# M420C.net
KiCad netlist of a schematic drawn in EAGLE
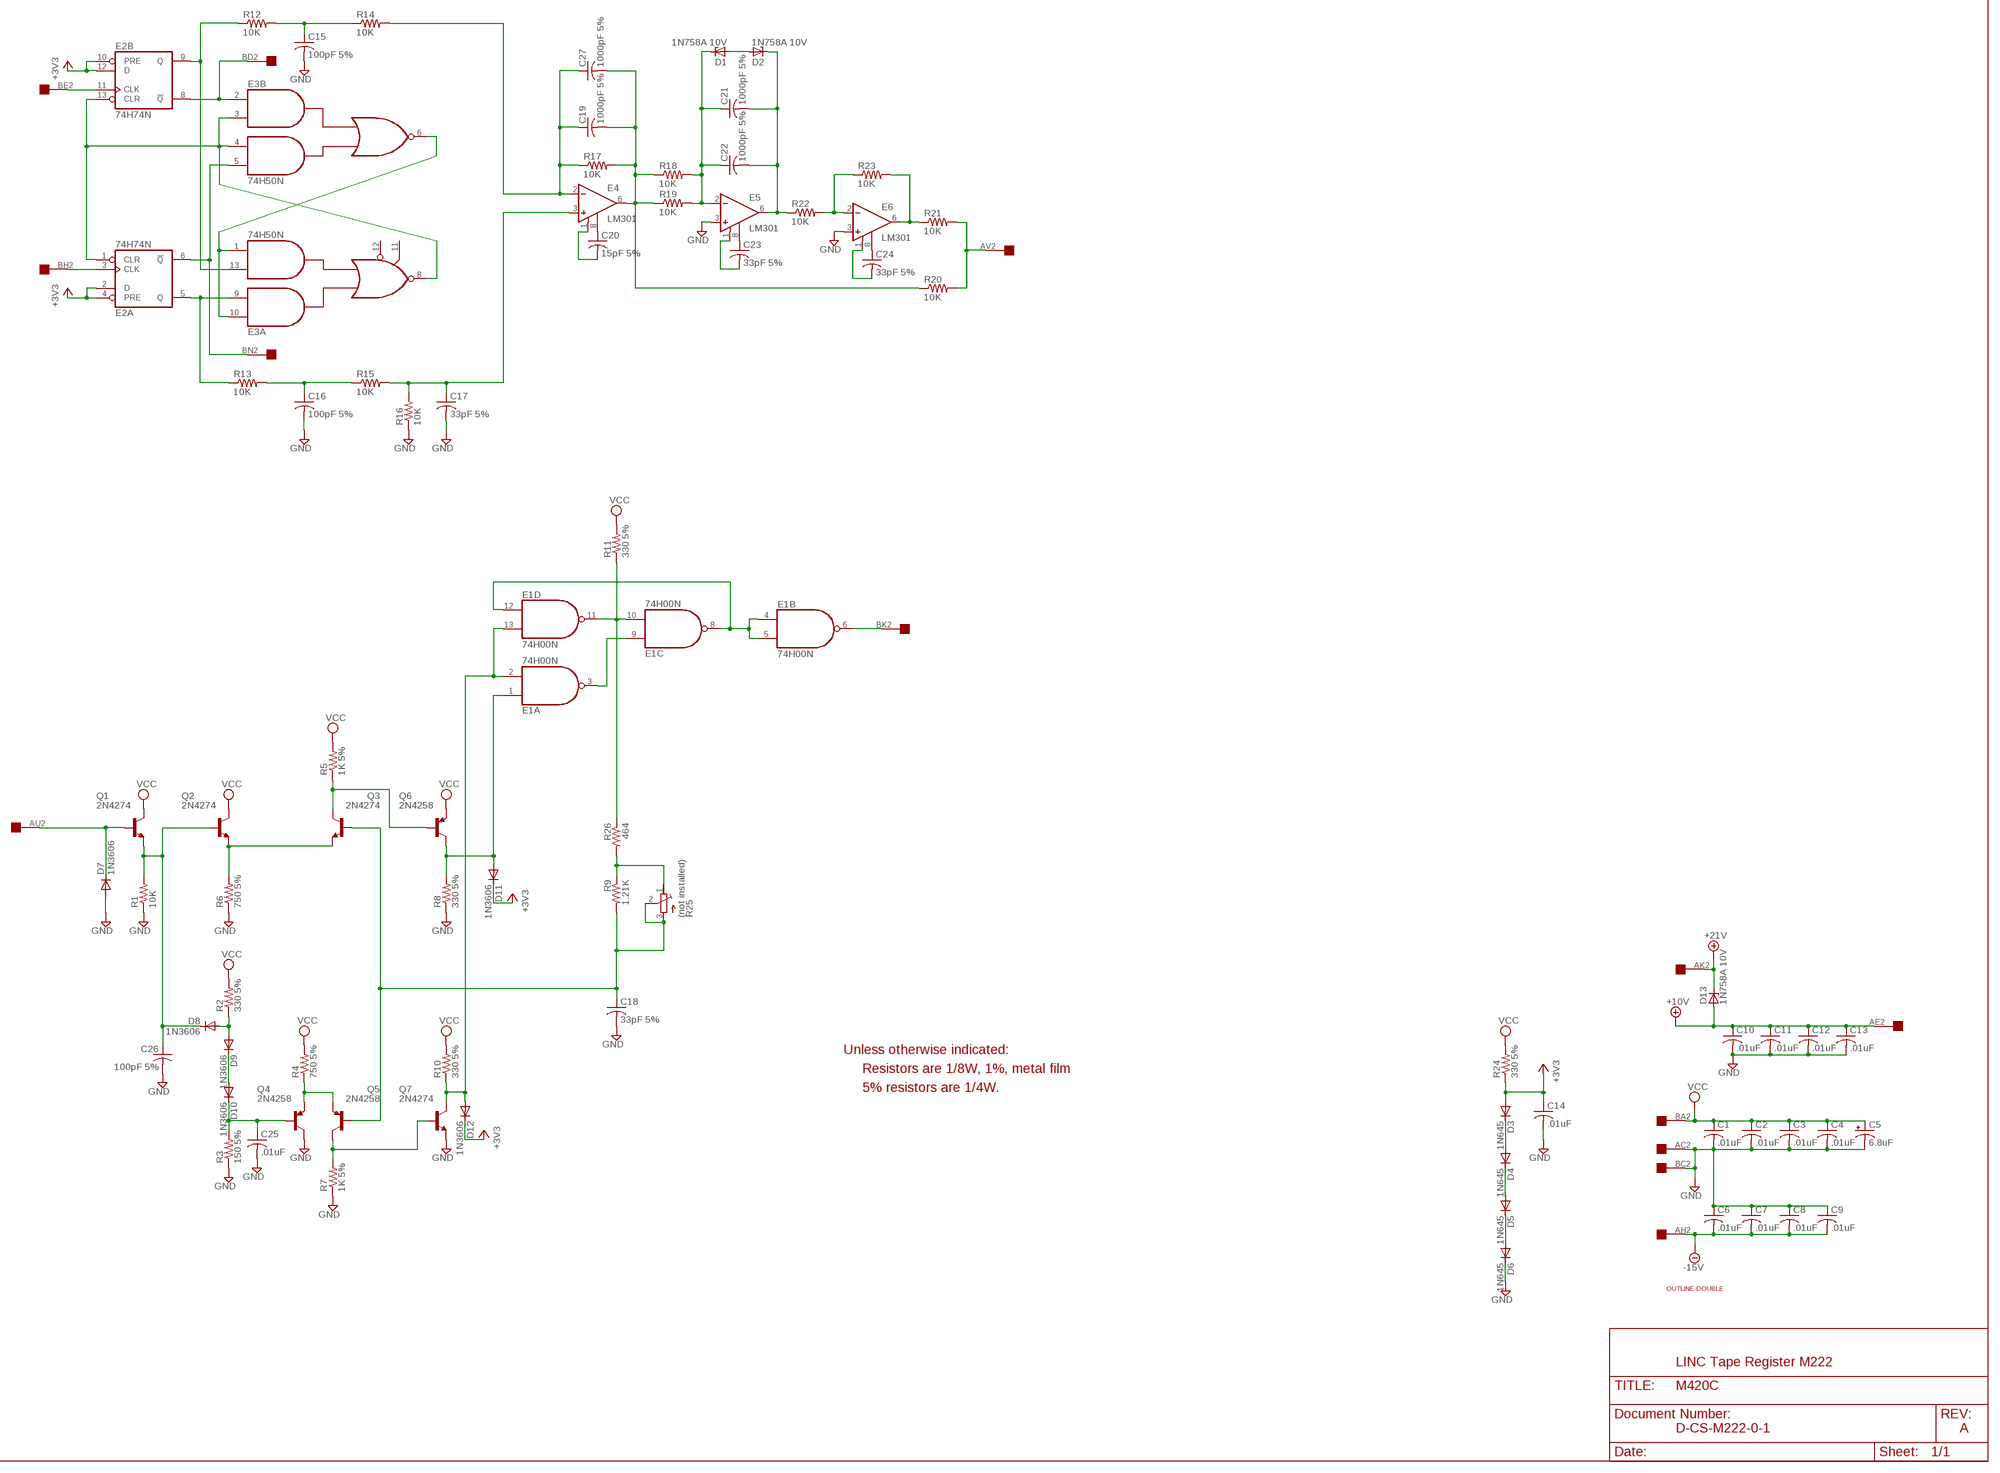
[diagram p0: schematic, sheet 1]

(export (version "E")
  (design (tool "Eeschema 10.0.6"))
  (components
    (comp (ref "C1")
      (value ".01uF")
      (footprint "eagle-import:C050-025X075")
      (libsource (lib "eagle-import") (part "C-US050-025X075"))
    )
    (comp (ref "C2")
      (value ".01uF")
      (footprint "eagle-import:C050-025X075")
      (libsource (lib "eagle-import") (part "C-US050-025X075"))
    )
    (comp (ref "C3")
      (value ".01uF")
      (footprint "eagle-import:C050-025X075")
      (libsource (lib "eagle-import") (part "C-US050-025X075"))
    )
    (comp (ref "C4")
      (value ".01uF")
      (footprint "eagle-import:C050-025X075")
      (libsource (lib "eagle-import") (part "C-US050-025X075"))
    )
    (comp (ref "C5")
      (value "6.8uF")
      (footprint "eagle-import:E12-8")
      (libsource (lib "eagle-import") (part "CPOL-USE20-8AXIAL"))
    )
    (comp (ref "C6")
      (value ".01uF")
      (footprint "eagle-import:C050-025X075")
      (libsource (lib "eagle-import") (part "C-US050-025X075"))
    )
    (comp (ref "C7")
      (value ".01uF")
      (footprint "eagle-import:C050-025X075")
      (libsource (lib "eagle-import") (part "C-US050-025X075"))
    )
    (comp (ref "C8")
      (value ".01uF")
      (footprint "eagle-import:C050-025X075")
      (libsource (lib "eagle-import") (part "C-US050-025X075"))
    )
    (comp (ref "C9")
      (value ".01uF")
      (footprint "eagle-import:C050-025X075")
      (libsource (lib "eagle-import") (part "C-US050-025X075"))
    )
    (comp (ref "C10")
      (value ".01uF")
      (footprint "eagle-import:C050-025X075")
      (libsource (lib "eagle-import") (part "C-US050-025X075"))
    )
    (comp (ref "C11")
      (value ".01uF")
      (footprint "eagle-import:C050-025X075")
      (libsource (lib "eagle-import") (part "C-US050-025X075"))
    )
    (comp (ref "C12")
      (value ".01uF")
      (footprint "eagle-import:C050-025X075")
      (libsource (lib "eagle-import") (part "C-US050-025X075"))
    )
    (comp (ref "C13")
      (value ".01uF")
      (footprint "eagle-import:C050-025X075")
      (libsource (lib "eagle-import") (part "C-US050-025X075"))
    )
    (comp (ref "C14")
      (value ".01uF")
      (footprint "eagle-import:C050-025X075")
      (libsource (lib "eagle-import") (part "C-US050-025X075"))
    )
    (comp (ref "C15")
      (value "100pF 5%")
      (footprint "eagle-import:C050-025X075")
      (libsource (lib "eagle-import") (part "C-US050-025X075"))
    )
    (comp (ref "C16")
      (value "100pF 5%")
      (footprint "eagle-import:C050-025X075")
      (libsource (lib "eagle-import") (part "C-US050-025X075"))
    )
    (comp (ref "C17")
      (value "33pF 5%")
      (footprint "eagle-import:C050-025X075")
      (libsource (lib "eagle-import") (part "C-US050-025X075"))
    )
    (comp (ref "C18")
      (value "33pF 5%")
      (footprint "eagle-import:C050-025X075")
      (libsource (lib "eagle-import") (part "C-US050-025X075"))
    )
    (comp (ref "C19")
      (value "1000pF 5%")
      (footprint "eagle-import:C050-025X075")
      (libsource (lib "eagle-import") (part "C-US050-025X075"))
    )
    (comp (ref "C20")
      (value "15pF 5%")
      (footprint "eagle-import:C050-025X075")
      (libsource (lib "eagle-import") (part "C-US050-025X075"))
    )
    (comp (ref "C21")
      (value "1000pF 5%")
      (footprint "eagle-import:C050-025X075")
      (libsource (lib "eagle-import") (part "C-US050-025X075"))
    )
    (comp (ref "C22")
      (value "1000pF 5%")
      (footprint "eagle-import:C050-025X075")
      (libsource (lib "eagle-import") (part "C-US050-025X075"))
    )
    (comp (ref "C23")
      (value "33pF 5%")
      (footprint "eagle-import:C050-025X075")
      (libsource (lib "eagle-import") (part "C-US050-025X075"))
    )
    (comp (ref "C24")
      (value "33pF 5%")
      (footprint "eagle-import:C050-025X075")
      (libsource (lib "eagle-import") (part "C-US050-025X075"))
    )
    (comp (ref "C25")
      (value ".01uF")
      (footprint "eagle-import:C050-025X075")
      (libsource (lib "eagle-import") (part "C-US050-025X075"))
    )
    (comp (ref "C26")
      (value "100pF 5%")
      (footprint "eagle-import:C050-025X075")
      (libsource (lib "eagle-import") (part "C-US050-025X075"))
    )
    (comp (ref "C27")
      (value "1000pF 5%")
      (footprint "eagle-import:C050-025X075")
      (libsource (lib "eagle-import") (part "C-US050-025X075"))
    )
    (comp (ref "D1")
      (value "1N758A 10V")
      (footprint "eagle-import:DO35Z10")
      (libsource (lib "eagle-import") (part "ZENER-DIODEDO35Z10"))
    )
    (comp (ref "D2")
      (value "1N758A 10V")
      (footprint "eagle-import:DO35Z10")
      (libsource (lib "eagle-import") (part "ZENER-DIODEDO35Z10"))
    )
    (comp (ref "D3")
      (value "1N645")
      (footprint "eagle-import:DO35-10")
      (libsource (lib "eagle-import") (part "1N4148DO35-10"))
    )
    (comp (ref "D4")
      (value "1N645")
      (footprint "eagle-import:DO35-10")
      (libsource (lib "eagle-import") (part "1N4148DO35-10"))
    )
    (comp (ref "D5")
      (value "1N645")
      (footprint "eagle-import:DO35-10")
      (libsource (lib "eagle-import") (part "1N4148DO35-10"))
    )
    (comp (ref "D6")
      (value "1N645")
      (footprint "eagle-import:DO35-10")
      (libsource (lib "eagle-import") (part "1N4148DO35-10"))
    )
    (comp (ref "D7")
      (value "1N3606")
      (footprint "eagle-import:DO35-10")
      (libsource (lib "eagle-import") (part "1N4148DO35-10"))
    )
    (comp (ref "D8")
      (value "1N3606")
      (footprint "eagle-import:DO35-10")
      (libsource (lib "eagle-import") (part "1N4148DO35-10"))
    )
    (comp (ref "D9")
      (value "1N3606")
      (footprint "eagle-import:DO35-10")
      (libsource (lib "eagle-import") (part "1N4148DO35-10"))
    )
    (comp (ref "D10")
      (value "1N3606")
      (footprint "eagle-import:DO35-10")
      (libsource (lib "eagle-import") (part "1N4148DO35-10"))
    )
    (comp (ref "D11")
      (value "1N3606")
      (footprint "eagle-import:DO35-10")
      (libsource (lib "eagle-import") (part "1N4148DO35-10"))
    )
    (comp (ref "D12")
      (value "1N3606")
      (footprint "eagle-import:DO35-10")
      (libsource (lib "eagle-import") (part "1N4148DO35-10"))
    )
    (comp (ref "D13")
      (value "1N758A 10V")
      (footprint "eagle-import:DO35Z10")
      (libsource (lib "eagle-import") (part "ZENER-DIODEDO35Z10"))
    )
    (comp (ref "E1")
      (value "74H00N")
      (footprint "eagle-import:DIL14")
      (libsource (lib "eagle-import") (part "7400N"))
    )
    (comp (ref "E2")
      (value "74H74N")
      (footprint "eagle-import:DIL14")
      (libsource (lib "eagle-import") (part "7474NS"))
    )
    (comp (ref "E3")
      (value "74H50N")
      (footprint "eagle-import:DIL14")
      (libsource (lib "eagle-import") (part "7450N"))
    )
    (comp (ref "E4")
      (value "LM301")
      (footprint "eagle-import:TO99")
      (libsource (lib "eagle-import") (part "LM301"))
    )
    (comp (ref "E5")
      (value "LM301")
      (footprint "eagle-import:TO99")
      (libsource (lib "eagle-import") (part "LM301"))
    )
    (comp (ref "E6")
      (value "LM301")
      (footprint "eagle-import:TO99")
      (libsource (lib "eagle-import") (part "LM301"))
    )
    (comp (ref "Q1")
      (value "2N4274")
      (footprint "eagle-import:TO5")
      (libsource (lib "eagle-import") (part "2N3439"))
    )
    (comp (ref "Q2")
      (value "2N4274")
      (footprint "eagle-import:TO5")
      (libsource (lib "eagle-import") (part "2N3439"))
    )
    (comp (ref "Q3")
      (value "2N4274")
      (footprint "eagle-import:TO5")
      (libsource (lib "eagle-import") (part "2N3439"))
    )
    (comp (ref "Q4")
      (value "2N4258")
      (footprint "eagle-import:TO39")
      (libsource (lib "eagle-import") (part "2N3635"))
    )
    (comp (ref "Q5")
      (value "2N4258")
      (footprint "eagle-import:TO39")
      (libsource (lib "eagle-import") (part "2N3635"))
    )
    (comp (ref "Q6")
      (value "2N4258")
      (footprint "eagle-import:TO39")
      (libsource (lib "eagle-import") (part "2N3635"))
    )
    (comp (ref "Q7")
      (value "2N4274")
      (footprint "eagle-import:TO5")
      (libsource (lib "eagle-import") (part "2N3439"))
    )
    (comp (ref "R1")
      (value "10K")
      (footprint "eagle-import:0207_15")
      (libsource (lib "eagle-import") (part "R-US_0207/15"))
    )
    (comp (ref "R2")
      (value "330 5%")
      (footprint "eagle-import:0207_10")
      (libsource (lib "eagle-import") (part "R-US_0207/10"))
    )
    (comp (ref "R3")
      (value "150 5%")
      (footprint "eagle-import:0207_10")
      (libsource (lib "eagle-import") (part "R-US_0207/10"))
    )
    (comp (ref "R4")
      (value "750 5%")
      (footprint "eagle-import:0207_10")
      (libsource (lib "eagle-import") (part "R-US_0207/10"))
    )
    (comp (ref "R5")
      (value "1K 5%")
      (footprint "eagle-import:0207_10")
      (libsource (lib "eagle-import") (part "R-US_0207/10"))
    )
    (comp (ref "R6")
      (value "750 5%")
      (footprint "eagle-import:0207_10")
      (libsource (lib "eagle-import") (part "R-US_0207/10"))
    )
    (comp (ref "R7")
      (value "1K 5%")
      (footprint "eagle-import:0207_10")
      (libsource (lib "eagle-import") (part "R-US_0207/10"))
    )
    (comp (ref "R8")
      (value "330 5%")
      (footprint "eagle-import:0207_10")
      (libsource (lib "eagle-import") (part "R-US_0207/10"))
    )
    (comp (ref "R9")
      (value "1.21K")
      (footprint "eagle-import:0207_15")
      (libsource (lib "eagle-import") (part "R-US_0207/15"))
    )
    (comp (ref "R10")
      (value "330 5%")
      (footprint "eagle-import:0207_10")
      (libsource (lib "eagle-import") (part "R-US_0207/10"))
    )
    (comp (ref "R11")
      (value "330 5%")
      (footprint "eagle-import:0207_10")
      (libsource (lib "eagle-import") (part "R-US_0207/10"))
    )
    (comp (ref "R12")
      (value "10K")
      (footprint "eagle-import:0207_15")
      (libsource (lib "eagle-import") (part "R-US_0207/15"))
    )
    (comp (ref "R13")
      (value "10K")
      (footprint "eagle-import:0207_15")
      (libsource (lib "eagle-import") (part "R-US_0207/15"))
    )
    (comp (ref "R14")
      (value "10K")
      (footprint "eagle-import:0207_15")
      (libsource (lib "eagle-import") (part "R-US_0207/15"))
    )
    (comp (ref "R15")
      (value "10K")
      (footprint "eagle-import:0207_15")
      (libsource (lib "eagle-import") (part "R-US_0207/15"))
    )
    (comp (ref "R16")
      (value "10K")
      (footprint "eagle-import:0207_15")
      (libsource (lib "eagle-import") (part "R-US_0207/15"))
    )
    (comp (ref "R17")
      (value "10K")
      (footprint "eagle-import:0207_15")
      (libsource (lib "eagle-import") (part "R-US_0207/15"))
    )
    (comp (ref "R18")
      (value "10K")
      (footprint "eagle-import:0207_15")
      (libsource (lib "eagle-import") (part "R-US_0207/15"))
    )
    (comp (ref "R19")
      (value "10K")
      (footprint "eagle-import:0207_15")
      (libsource (lib "eagle-import") (part "R-US_0207/15"))
    )
    (comp (ref "R20")
      (value "10K")
      (footprint "eagle-import:0207_15")
      (libsource (lib "eagle-import") (part "R-US_0207/15"))
    )
    (comp (ref "R21")
      (value "10K")
      (footprint "eagle-import:0207_15")
      (libsource (lib "eagle-import") (part "R-US_0207/15"))
    )
    (comp (ref "R22")
      (value "10K")
      (footprint "eagle-import:0207_15")
      (libsource (lib "eagle-import") (part "R-US_0207/15"))
    )
    (comp (ref "R23")
      (value "10K")
      (footprint "eagle-import:0207_15")
      (libsource (lib "eagle-import") (part "R-US_0207/15"))
    )
    (comp (ref "R24")
      (value "330 5%")
      (footprint "eagle-import:0207_10")
      (libsource (lib "eagle-import") (part "R-US_0207/10"))
    )
    (comp (ref "R25")
      (value "(not installed)")
      (footprint "eagle-import:3006Y")
      (libsource (lib "eagle-import") (part "275P"))
    )
    (comp (ref "R26")
      (value "464")
      (footprint "eagle-import:0207_15")
      (libsource (lib "eagle-import") (part "R-US_0207/15"))
    )
    (comp (ref "U$1")
      (value "DOUBLE")
      (footprint "eagle-import:EDGE-CON4")
      (libsource (lib "eagle-import") (part "DOUBLE"))
    )
    (comp (ref "U$2")
      (value "OUTLINE-DOUBLE")
      (footprint "eagle-import:DOUBLE")
      (libsource (lib "eagle-import") (part "OUTLINE-DOUBLE"))
    )
  )
  (nets
    (net (code "1") (name "+3V3") (class "Default")
      (node (ref "C14") (pin "1") (pinfunction "1_1") (pintype "passive"))
      (node (ref "D11") (pin "C") (pinfunction "C_C") (pintype "passive"))
      (node (ref "D12") (pin "C") (pinfunction "C_C") (pintype "passive"))
      (node (ref "D3") (pin "A") (pinfunction "A_A") (pintype "passive"))
      (node (ref "E2") (pin "10") (pinfunction "PRE_10") (pintype "input"))
      (node (ref "E2") (pin "12") (pinfunction "D_12") (pintype "input"))
      (node (ref "E2") (pin "2") (pinfunction "D_2") (pintype "input"))
      (node (ref "E2") (pin "4") (pinfunction "PRE_4") (pintype "input"))
      (node (ref "R24") (pin "1") (pinfunction "1_1") (pintype "passive"))
    )
    (net (code "2") (name "+10V") (class "Default")
      (node (ref "C10") (pin "1") (pinfunction "1_1") (pintype "passive"))
      (node (ref "C11") (pin "1") (pinfunction "1_1") (pintype "passive"))
      (node (ref "C12") (pin "1") (pinfunction "1_1") (pintype "passive"))
      (node (ref "C13") (pin "1") (pinfunction "1_1") (pintype "passive"))
      (node (ref "D13") (pin "A") (pinfunction "A_A") (pintype "passive"))
      (node (ref "U$1") (pin "AE2") (pinfunction "1_AE2") (pintype "bidirectional"))
    )
    (net (code "3") (name "+21V") (class "Default")
      (node (ref "D13") (pin "C") (pinfunction "C_C") (pintype "passive"))
      (node (ref "U$1") (pin "AK2") (pinfunction "1_AK2") (pintype "bidirectional"))
    )
    (net (code "4") (name "-15V") (class "Default")
      (node (ref "C6") (pin "2") (pinfunction "2_2") (pintype "passive"))
      (node (ref "C7") (pin "2") (pinfunction "2_2") (pintype "passive"))
      (node (ref "C8") (pin "2") (pinfunction "2_2") (pintype "passive"))
      (node (ref "C9") (pin "2") (pinfunction "2_2") (pintype "passive"))
      (node (ref "U$1") (pin "AH2") (pinfunction "1_AH2") (pintype "bidirectional"))
    )
    (net (code "5") (name "GND") (class "Default")
      (node (ref "C1") (pin "2") (pinfunction "2_2") (pintype "passive"))
      (node (ref "C10") (pin "2") (pinfunction "2_2") (pintype "passive"))
      (node (ref "C11") (pin "2") (pinfunction "2_2") (pintype "passive"))
      (node (ref "C12") (pin "2") (pinfunction "2_2") (pintype "passive"))
      (node (ref "C13") (pin "2") (pinfunction "2_2") (pintype "passive"))
      (node (ref "C14") (pin "2") (pinfunction "2_2") (pintype "passive"))
      (node (ref "C15") (pin "2") (pinfunction "2_2") (pintype "passive"))
      (node (ref "C16") (pin "2") (pinfunction "2_2") (pintype "passive"))
      (node (ref "C17") (pin "2") (pinfunction "2_2") (pintype "passive"))
      (node (ref "C18") (pin "2") (pinfunction "2_2") (pintype "passive"))
      (node (ref "C2") (pin "2") (pinfunction "2_2") (pintype "passive"))
      (node (ref "C25") (pin "2") (pinfunction "2_2") (pintype "passive"))
      (node (ref "C26") (pin "2") (pinfunction "2_2") (pintype "passive"))
      (node (ref "C3") (pin "2") (pinfunction "2_2") (pintype "passive"))
      (node (ref "C4") (pin "2") (pinfunction "2_2") (pintype "passive"))
      (node (ref "C5") (pin "-") (pinfunction "-_-") (pintype "passive"))
      (node (ref "C6") (pin "1") (pinfunction "1_1") (pintype "passive"))
      (node (ref "C7") (pin "1") (pinfunction "1_1") (pintype "passive"))
      (node (ref "C8") (pin "1") (pinfunction "1_1") (pintype "passive"))
      (node (ref "C9") (pin "1") (pinfunction "1_1") (pintype "passive"))
      (node (ref "D6") (pin "C") (pinfunction "C_C") (pintype "passive"))
      (node (ref "D7") (pin "A") (pinfunction "A_A") (pintype "passive"))
      (node (ref "E5") (pin "3") (pinfunction "+IN_3") (pintype "input"))
      (node (ref "E6") (pin "3") (pinfunction "+IN_3") (pintype "input"))
      (node (ref "Q4") (pin "3") (pinfunction "C_3") (pintype "passive"))
      (node (ref "Q7") (pin "1") (pinfunction "E_1") (pintype "passive"))
      (node (ref "R1") (pin "1") (pinfunction "1_1") (pintype "passive"))
      (node (ref "R16") (pin "1") (pinfunction "1_1") (pintype "passive"))
      (node (ref "R3") (pin "1") (pinfunction "1_1") (pintype "passive"))
      (node (ref "R6") (pin "1") (pinfunction "1_1") (pintype "passive"))
      (node (ref "R7") (pin "1") (pinfunction "1_1") (pintype "passive"))
      (node (ref "R8") (pin "1") (pinfunction "1_1") (pintype "passive"))
      (node (ref "U$1") (pin "AC2") (pinfunction "1_AC2") (pintype "bidirectional"))
      (node (ref "U$1") (pin "BC2") (pinfunction "1_BC2") (pintype "bidirectional"))
    )
    (net (code "6") (name "Net-(C15-Pad1)") (class "Default")
      (node (ref "C15") (pin "1") (pinfunction "1_1") (pintype "passive"))
      (node (ref "R12") (pin "2") (pinfunction "2_2") (pintype "passive"))
      (node (ref "R14") (pin "1") (pinfunction "1_1") (pintype "passive"))
    )
    (net (code "7") (name "Net-(C16-Pad1)") (class "Default")
      (node (ref "C16") (pin "1") (pinfunction "1_1") (pintype "passive"))
      (node (ref "R13") (pin "2") (pinfunction "2_2") (pintype "passive"))
      (node (ref "R15") (pin "1") (pinfunction "1_1") (pintype "passive"))
    )
    (net (code "8") (name "Net-(D1-PadA)") (class "Default")
      (node (ref "D1") (pin "A") (pinfunction "A_A") (pintype "passive"))
      (node (ref "D2") (pin "A") (pinfunction "A_A") (pintype "passive"))
    )
    (net (code "9") (name "Net-(D3-PadC)") (class "Default")
      (node (ref "D3") (pin "C") (pinfunction "C_C") (pintype "passive"))
      (node (ref "D4") (pin "A") (pinfunction "A_A") (pintype "passive"))
    )
    (net (code "10") (name "Net-(D4-PadC)") (class "Default")
      (node (ref "D4") (pin "C") (pinfunction "C_C") (pintype "passive"))
      (node (ref "D5") (pin "A") (pinfunction "A_A") (pintype "passive"))
    )
    (net (code "11") (name "Net-(D5-PadC)") (class "Default")
      (node (ref "D5") (pin "C") (pinfunction "C_C") (pintype "passive"))
      (node (ref "D6") (pin "A") (pinfunction "A_A") (pintype "passive"))
    )
    (net (code "12") (name "Net-(D8-PadA)") (class "Default")
      (node (ref "D8") (pin "A") (pinfunction "A_A") (pintype "passive"))
      (node (ref "D9") (pin "A") (pinfunction "A_A") (pintype "passive"))
      (node (ref "R2") (pin "1") (pinfunction "1_1") (pintype "passive"))
    )
    (net (code "13") (name "Net-(D10-PadA)") (class "Default")
      (node (ref "D10") (pin "A") (pinfunction "A_A") (pintype "passive"))
      (node (ref "D9") (pin "C") (pinfunction "C_C") (pintype "passive"))
    )
    (net (code "14") (name "Net-(E1A-I0)") (class "Default")
      (node (ref "D11") (pin "A") (pinfunction "A_A") (pintype "passive"))
      (node (ref "E1") (pin "1") (pinfunction "I0_1") (pintype "input"))
      (node (ref "Q6") (pin "3") (pinfunction "C_3") (pintype "passive"))
      (node (ref "R8") (pin "2") (pinfunction "2_2") (pintype "passive"))
    )
    (net (code "15") (name "Net-(E1A-I1)") (class "Default")
      (node (ref "D12") (pin "A") (pinfunction "A_A") (pintype "passive"))
      (node (ref "E1") (pin "13") (pinfunction "I1_13") (pintype "input"))
      (node (ref "E1") (pin "2") (pinfunction "I1_2") (pintype "input"))
      (node (ref "Q7") (pin "3") (pinfunction "C_3") (pintype "passive"))
      (node (ref "R10") (pin "1") (pinfunction "1_1") (pintype "passive"))
    )
    (net (code "16") (name "Net-(E1A-O)") (class "Default")
      (node (ref "E1") (pin "3") (pinfunction "O_3") (pintype "output"))
      (node (ref "E1") (pin "9") (pinfunction "I0_9") (pintype "input"))
    )
    (net (code "17") (name "Net-(E1B-I0)") (class "Default")
      (node (ref "E1") (pin "12") (pinfunction "I0_12") (pintype "input"))
      (node (ref "E1") (pin "4") (pinfunction "I0_4") (pintype "input"))
      (node (ref "E1") (pin "5") (pinfunction "I1_5") (pintype "input"))
      (node (ref "E1") (pin "8") (pinfunction "O_8") (pintype "output"))
    )
    (net (code "18") (name "Net-(E1B-O)") (class "Default")
      (node (ref "E1") (pin "6") (pinfunction "O_6") (pintype "output"))
      (node (ref "U$1") (pin "BK2") (pinfunction "1_BK2") (pintype "bidirectional"))
    )
    (net (code "19") (name "Net-(E1C-I1)") (class "Default")
      (node (ref "E1") (pin "10") (pinfunction "I1_10") (pintype "input"))
      (node (ref "E1") (pin "11") (pinfunction "O_11") (pintype "output"))
      (node (ref "R11") (pin "1") (pinfunction "1_1") (pintype "passive"))
      (node (ref "R26") (pin "1") (pinfunction "1_1") (pintype "passive"))
    )
    (net (code "20") (name "Net-(E2A-CLK)") (class "Default")
      (node (ref "E2") (pin "3") (pinfunction "CLK_3") (pintype "input"))
      (node (ref "U$1") (pin "BH2") (pinfunction "1_BH2") (pintype "bidirectional"))
    )
    (net (code "21") (name "Net-(E2A-CLR)") (class "Default")
      (node (ref "E2") (pin "1") (pinfunction "CLR_1") (pintype "input"))
      (node (ref "E2") (pin "13") (pinfunction "CLR_13") (pintype "input"))
      (node (ref "E3") (pin "3") (pinfunction "I2_3") (pintype "input"))
      (node (ref "E3") (pin "4") (pinfunction "I3_4") (pintype "input"))
      (node (ref "E3") (pin "8") (pinfunction "O_8") (pintype "output"))
    )
    (net (code "22") (name "Net-(E2A-Q)") (class "Default")
      (node (ref "E2") (pin "5") (pinfunction "Q_5") (pintype "output"))
      (node (ref "E3") (pin "9") (pinfunction "I2_9") (pintype "input"))
      (node (ref "R13") (pin "1") (pinfunction "1_1") (pintype "passive"))
    )
    (net (code "23") (name "Net-(E2A-~{Q})") (class "Default")
      (node (ref "E2") (pin "6") (pinfunction "~{Q}_6") (pintype "output"))
      (node (ref "E3") (pin "5") (pinfunction "I4_5") (pintype "input"))
      (node (ref "U$1") (pin "BN2") (pinfunction "1_BN2") (pintype "bidirectional"))
    )
    (net (code "24") (name "Net-(E2B-CLK)") (class "Default")
      (node (ref "E2") (pin "11") (pinfunction "CLK_11") (pintype "input"))
      (node (ref "U$1") (pin "BE2") (pinfunction "1_BE2") (pintype "bidirectional"))
    )
    (net (code "25") (name "Net-(E2B-Q)") (class "Default")
      (node (ref "E2") (pin "9") (pinfunction "Q_9") (pintype "output"))
      (node (ref "E3") (pin "13") (pinfunction "I3_13") (pintype "input"))
      (node (ref "R12") (pin "1") (pinfunction "1_1") (pintype "passive"))
    )
    (net (code "26") (name "Net-(E2B-~{Q})") (class "Default")
      (node (ref "E2") (pin "8") (pinfunction "~{Q}_8") (pintype "output"))
      (node (ref "E3") (pin "2") (pinfunction "I1_2") (pintype "input"))
      (node (ref "U$1") (pin "BD2") (pinfunction "1_BD2") (pintype "bidirectional"))
    )
    (net (code "27") (name "Net-(E3A-I1)") (class "Default")
      (node (ref "E3") (pin "1") (pinfunction "I4_1") (pintype "input"))
      (node (ref "E3") (pin "10") (pinfunction "I1_10") (pintype "input"))
      (node (ref "E3") (pin "6") (pinfunction "O_6") (pintype "output"))
    )
    (net (code "28") (name "Net-(E4A-+IN)") (class "Default")
      (node (ref "C17") (pin "1") (pinfunction "1_1") (pintype "passive"))
      (node (ref "E4") (pin "3") (pinfunction "+IN_3") (pintype "input"))
      (node (ref "R15") (pin "2") (pinfunction "2_2") (pintype "passive"))
      (node (ref "R16") (pin "2") (pinfunction "2_2") (pintype "passive"))
    )
    (net (code "29") (name "Net-(E4A--IN)") (class "Default")
      (node (ref "C19") (pin "1") (pinfunction "1_1") (pintype "passive"))
      (node (ref "C27") (pin "1") (pinfunction "1_1") (pintype "passive"))
      (node (ref "E4") (pin "2") (pinfunction "-IN_2") (pintype "input"))
      (node (ref "R14") (pin "2") (pinfunction "2_2") (pintype "passive"))
      (node (ref "R17") (pin "1") (pinfunction "1_1") (pintype "passive"))
    )
    (net (code "30") (name "Net-(E4A-CMP)") (class "Default")
      (node (ref "C20") (pin "1") (pinfunction "1_1") (pintype "passive"))
      (node (ref "E4") (pin "8") (pinfunction "CMP_8") (pintype "passive"))
    )
    (net (code "31") (name "Net-(E4A-ON{slash}CMP)") (class "Default")
      (node (ref "C20") (pin "2") (pinfunction "2_2") (pintype "passive"))
      (node (ref "E4") (pin "1") (pinfunction "ON/CMP_1") (pintype "passive"))
    )
    (net (code "32") (name "Net-(E4A-OUT)") (class "Default")
      (node (ref "C19") (pin "2") (pinfunction "2_2") (pintype "passive"))
      (node (ref "C27") (pin "2") (pinfunction "2_2") (pintype "passive"))
      (node (ref "E4") (pin "6") (pinfunction "OUT_6") (pintype "output"))
      (node (ref "R17") (pin "2") (pinfunction "2_2") (pintype "passive"))
      (node (ref "R18") (pin "1") (pinfunction "1_1") (pintype "passive"))
      (node (ref "R19") (pin "1") (pinfunction "1_1") (pintype "passive"))
      (node (ref "R20") (pin "1") (pinfunction "1_1") (pintype "passive"))
    )
    (net (code "33") (name "Net-(E5A--IN)") (class "Default")
      (node (ref "C21") (pin "1") (pinfunction "1_1") (pintype "passive"))
      (node (ref "C22") (pin "1") (pinfunction "1_1") (pintype "passive"))
      (node (ref "D1") (pin "C") (pinfunction "C_C") (pintype "passive"))
      (node (ref "E5") (pin "2") (pinfunction "-IN_2") (pintype "input"))
      (node (ref "R18") (pin "2") (pinfunction "2_2") (pintype "passive"))
      (node (ref "R19") (pin "2") (pinfunction "2_2") (pintype "passive"))
    )
    (net (code "34") (name "Net-(E5A-CMP)") (class "Default")
      (node (ref "C23") (pin "1") (pinfunction "1_1") (pintype "passive"))
      (node (ref "E5") (pin "8") (pinfunction "CMP_8") (pintype "passive"))
    )
    (net (code "35") (name "Net-(E5A-ON{slash}CMP)") (class "Default")
      (node (ref "C23") (pin "2") (pinfunction "2_2") (pintype "passive"))
      (node (ref "E5") (pin "1") (pinfunction "ON/CMP_1") (pintype "passive"))
    )
    (net (code "36") (name "Net-(E5A-OUT)") (class "Default")
      (node (ref "C21") (pin "2") (pinfunction "2_2") (pintype "passive"))
      (node (ref "C22") (pin "2") (pinfunction "2_2") (pintype "passive"))
      (node (ref "D2") (pin "C") (pinfunction "C_C") (pintype "passive"))
      (node (ref "E5") (pin "6") (pinfunction "OUT_6") (pintype "output"))
      (node (ref "R22") (pin "1") (pinfunction "1_1") (pintype "passive"))
    )
    (net (code "37") (name "Net-(E6A--IN)") (class "Default")
      (node (ref "E6") (pin "2") (pinfunction "-IN_2") (pintype "input"))
      (node (ref "R22") (pin "2") (pinfunction "2_2") (pintype "passive"))
      (node (ref "R23") (pin "1") (pinfunction "1_1") (pintype "passive"))
    )
    (net (code "38") (name "Net-(E6A-CMP)") (class "Default")
      (node (ref "C24") (pin "1") (pinfunction "1_1") (pintype "passive"))
      (node (ref "E6") (pin "8") (pinfunction "CMP_8") (pintype "passive"))
    )
    (net (code "39") (name "Net-(E6A-ON{slash}CMP)") (class "Default")
      (node (ref "C24") (pin "2") (pinfunction "2_2") (pintype "passive"))
      (node (ref "E6") (pin "1") (pinfunction "ON/CMP_1") (pintype "passive"))
    )
    (net (code "40") (name "Net-(E6A-OUT)") (class "Default")
      (node (ref "E6") (pin "6") (pinfunction "OUT_6") (pintype "output"))
      (node (ref "R21") (pin "1") (pinfunction "1_1") (pintype "passive"))
      (node (ref "R23") (pin "2") (pinfunction "2_2") (pintype "passive"))
    )
    (net (code "41") (name "Net-(Q1-B)") (class "Default")
      (node (ref "D7") (pin "C") (pinfunction "C_C") (pintype "passive"))
      (node (ref "Q1") (pin "2") (pinfunction "B_2") (pintype "passive"))
      (node (ref "U$1") (pin "AU2") (pinfunction "1_AU2") (pintype "bidirectional"))
    )
    (net (code "42") (name "Net-(Q1-E)") (class "Default")
      (node (ref "C26") (pin "1") (pinfunction "1_1") (pintype "passive"))
      (node (ref "D8") (pin "C") (pinfunction "C_C") (pintype "passive"))
      (node (ref "Q1") (pin "1") (pinfunction "E_1") (pintype "passive"))
      (node (ref "Q2") (pin "2") (pinfunction "B_2") (pintype "passive"))
      (node (ref "R1") (pin "2") (pinfunction "2_2") (pintype "passive"))
    )
    (net (code "43") (name "Net-(Q2-E)") (class "Default")
      (node (ref "Q2") (pin "1") (pinfunction "E_1") (pintype "passive"))
      (node (ref "Q3") (pin "1") (pinfunction "E_1") (pintype "passive"))
      (node (ref "R6") (pin "2") (pinfunction "2_2") (pintype "passive"))
    )
    (net (code "44") (name "Net-(Q3-B)") (class "Default")
      (node (ref "C18") (pin "1") (pinfunction "1_1") (pintype "passive"))
      (node (ref "Q3") (pin "2") (pinfunction "B_2") (pintype "passive"))
      (node (ref "Q5") (pin "2") (pinfunction "B_2") (pintype "passive"))
      (node (ref "R25") (pin "2") (pinfunction "S_2") (pintype "passive"))
      (node (ref "R25") (pin "3") (pinfunction "E_3") (pintype "passive"))
      (node (ref "R9") (pin "2") (pinfunction "2_2") (pintype "passive"))
    )
    (net (code "45") (name "Net-(Q3-C)") (class "Default")
      (node (ref "Q3") (pin "3") (pinfunction "C_3") (pintype "passive"))
      (node (ref "Q6") (pin "2") (pinfunction "B_2") (pintype "passive"))
      (node (ref "R5") (pin "1") (pinfunction "1_1") (pintype "passive"))
    )
    (net (code "46") (name "Net-(Q4-B)") (class "Default")
      (node (ref "C25") (pin "1") (pinfunction "1_1") (pintype "passive"))
      (node (ref "D10") (pin "C") (pinfunction "C_C") (pintype "passive"))
      (node (ref "Q4") (pin "2") (pinfunction "B_2") (pintype "passive"))
      (node (ref "R3") (pin "2") (pinfunction "2_2") (pintype "passive"))
    )
    (net (code "47") (name "Net-(Q4-E)") (class "Default")
      (node (ref "Q4") (pin "1") (pinfunction "E_1") (pintype "passive"))
      (node (ref "Q5") (pin "1") (pinfunction "E_1") (pintype "passive"))
      (node (ref "R4") (pin "1") (pinfunction "1_1") (pintype "passive"))
    )
    (net (code "48") (name "Net-(Q5-C)") (class "Default")
      (node (ref "Q5") (pin "3") (pinfunction "C_3") (pintype "passive"))
      (node (ref "Q7") (pin "2") (pinfunction "B_2") (pintype "passive"))
      (node (ref "R7") (pin "2") (pinfunction "2_2") (pintype "passive"))
    )
    (net (code "49") (name "Net-(R25-A)") (class "Default")
      (node (ref "R25") (pin "1") (pinfunction "A_1") (pintype "passive"))
      (node (ref "R26") (pin "2") (pinfunction "2_2") (pintype "passive"))
      (node (ref "R9") (pin "1") (pinfunction "1_1") (pintype "passive"))
    )
    (net (code "50") (name "Net-(U$1AJ-1)") (class "Default")
      (node (ref "R20") (pin "2") (pinfunction "2_2") (pintype "passive"))
      (node (ref "R21") (pin "2") (pinfunction "2_2") (pintype "passive"))
      (node (ref "U$1") (pin "AV2") (pinfunction "1_AV2") (pintype "bidirectional"))
    )
    (net (code "51") (name "VCC") (class "Default")
      (node (ref "C1") (pin "1") (pinfunction "1_1") (pintype "passive"))
      (node (ref "C2") (pin "1") (pinfunction "1_1") (pintype "passive"))
      (node (ref "C3") (pin "1") (pinfunction "1_1") (pintype "passive"))
      (node (ref "C4") (pin "1") (pinfunction "1_1") (pintype "passive"))
      (node (ref "C5") (pin "+") (pinfunction "+_+") (pintype "passive"))
      (node (ref "Q1") (pin "3") (pinfunction "C_3") (pintype "passive"))
      (node (ref "Q2") (pin "3") (pinfunction "C_3") (pintype "passive"))
      (node (ref "Q6") (pin "1") (pinfunction "E_1") (pintype "passive"))
      (node (ref "R10") (pin "2") (pinfunction "2_2") (pintype "passive"))
      (node (ref "R11") (pin "2") (pinfunction "2_2") (pintype "passive"))
      (node (ref "R2") (pin "2") (pinfunction "2_2") (pintype "passive"))
      (node (ref "R24") (pin "2") (pinfunction "2_2") (pintype "passive"))
      (node (ref "R4") (pin "2") (pinfunction "2_2") (pintype "passive"))
      (node (ref "R5") (pin "2") (pinfunction "2_2") (pintype "passive"))
      (node (ref "U$1") (pin "BA2") (pinfunction "1_BA2") (pintype "bidirectional"))
    )
    (net (code "52") (name "unconnected-(E3A-I5-Pad12)") (class "Default")
      (node (ref "E3") (pin "12") (pinfunction "I5_12") (pintype "passive"))
    )
    (net (code "53") (name "unconnected-(E3A-I6-Pad11)") (class "Default")
      (node (ref "E3") (pin "11") (pinfunction "I6_11") (pintype "passive"))
    )
  )
)
